# STM32F413CG_CS43L22.net
KiCad netlist of a schematic drawn in EAGLE
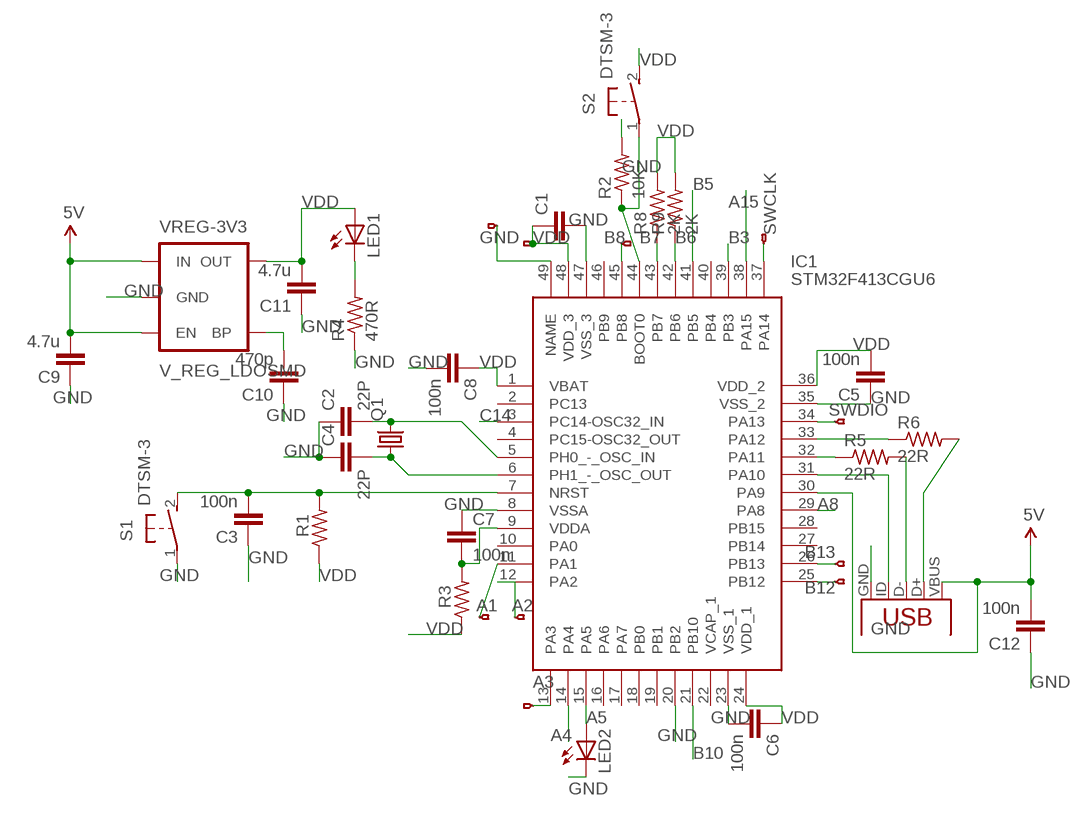
[diagram p0: schematic, sheet 1]
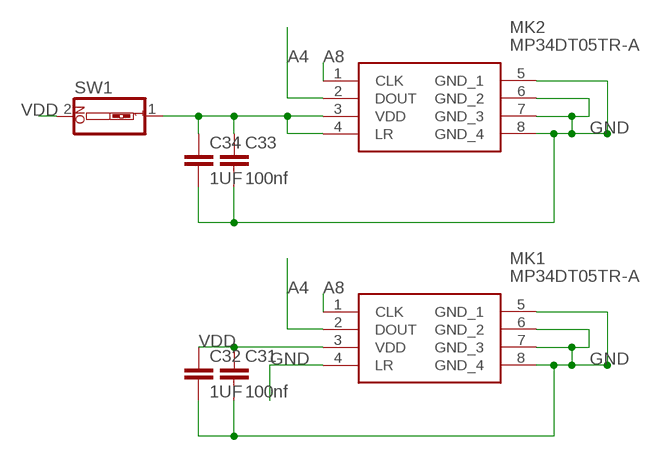
[diagram p1: schematic, sheet 2]
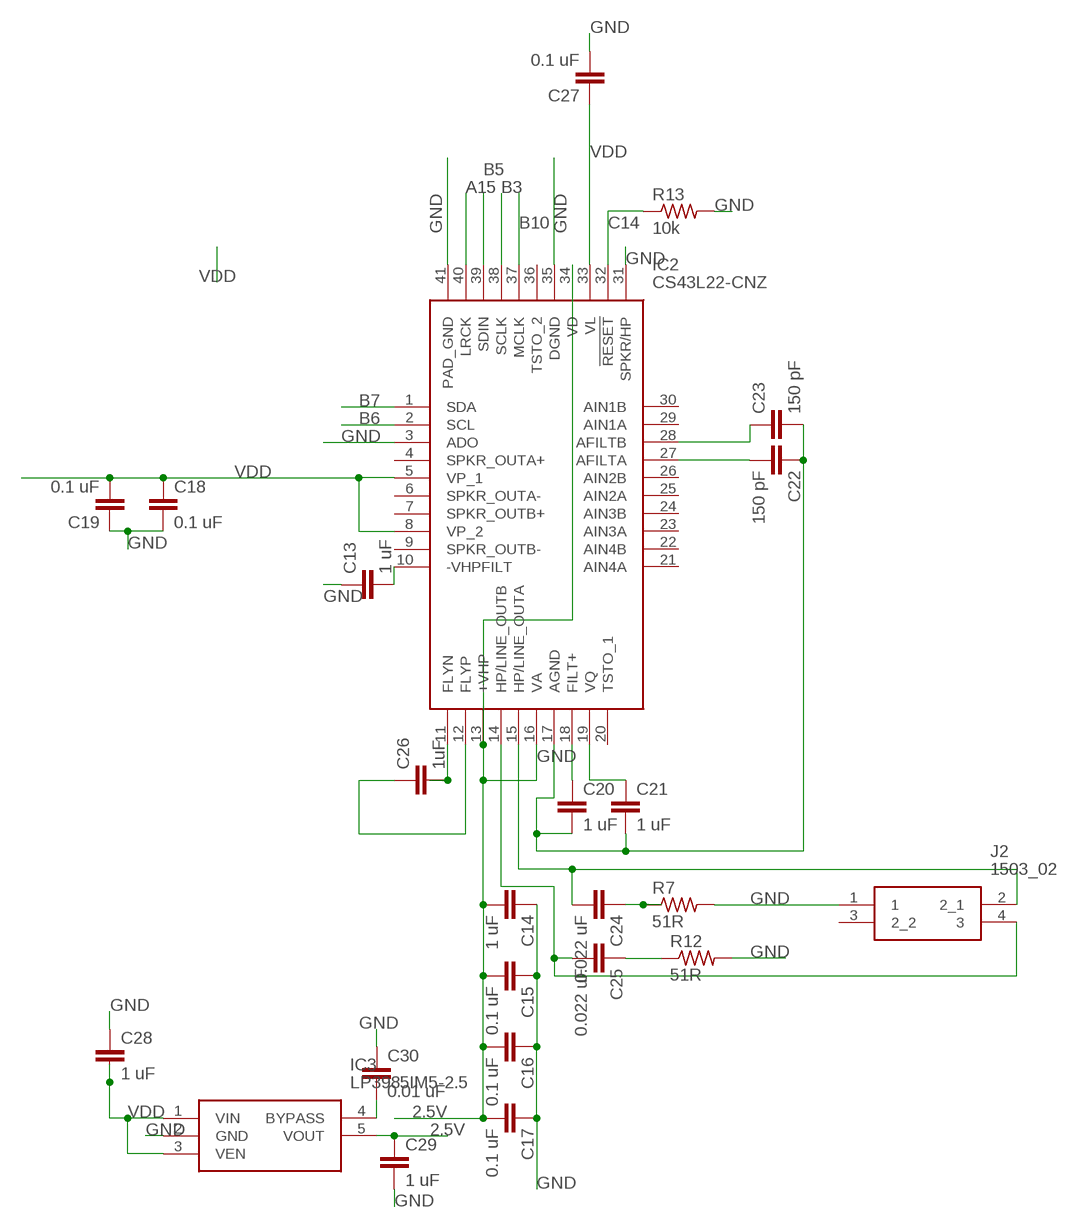
[diagram p2: schematic, sheet 3]

(export (version "E")
  (design (tool "Eeschema 10.0.6"))
  (components
    (comp (ref "C13")
      (value "1 uF")
      (footprint "eagle-import:CAP-PTH-SMALL-KIT")
      (libsource (lib "eagle-import") (part "CAPKIT"))
    )
    (comp (ref "C14")
      (value "1 uF")
      (footprint "eagle-import:CAP-PTH-SMALL-KIT")
      (libsource (lib "eagle-import") (part "CAPKIT"))
    )
    (comp (ref "C15")
      (value "0.1 uF")
      (footprint "eagle-import:CAP-PTH-SMALL-KIT")
      (libsource (lib "eagle-import") (part "CAPKIT"))
    )
    (comp (ref "C16")
      (value "0.1 uF")
      (footprint "eagle-import:CAP-PTH-SMALL-KIT")
      (libsource (lib "eagle-import") (part "CAPKIT"))
    )
    (comp (ref "C17")
      (value "0.1 uF")
      (footprint "eagle-import:CAP-PTH-SMALL-KIT")
      (libsource (lib "eagle-import") (part "CAPKIT"))
    )
    (comp (ref "C18")
      (value "0.1 uF")
      (footprint "eagle-import:CAP-PTH-SMALL-KIT")
      (libsource (lib "eagle-import") (part "CAPKIT"))
    )
    (comp (ref "C19")
      (value "0.1 uF")
      (footprint "eagle-import:CAP-PTH-SMALL-KIT")
      (libsource (lib "eagle-import") (part "CAPKIT"))
    )
    (comp (ref "C20")
      (value "1 uF")
      (footprint "eagle-import:CAP-PTH-SMALL-KIT")
      (libsource (lib "eagle-import") (part "CAPKIT"))
    )
    (comp (ref "C21")
      (value "1 uF")
      (footprint "eagle-import:CAP-PTH-SMALL-KIT")
      (libsource (lib "eagle-import") (part "CAPKIT"))
    )
    (comp (ref "C22")
      (value "150 pF")
      (footprint "eagle-import:CAP-PTH-SMALL-KIT")
      (libsource (lib "eagle-import") (part "CAPKIT"))
    )
    (comp (ref "C23")
      (value "150 pF")
      (footprint "eagle-import:CAP-PTH-SMALL-KIT")
      (libsource (lib "eagle-import") (part "CAPKIT"))
    )
    (comp (ref "C24")
      (value "0.022 uF")
      (footprint "eagle-import:CAP-PTH-SMALL-KIT")
      (libsource (lib "eagle-import") (part "CAPKIT"))
    )
    (comp (ref "C25")
      (value "0.022 uF")
      (footprint "eagle-import:CAP-PTH-SMALL-KIT")
      (libsource (lib "eagle-import") (part "CAPKIT"))
    )
    (comp (ref "C26")
      (value "1uF")
      (footprint "eagle-import:C2.5-3")
      (libsource (lib "eagle-import") (part "C2,5-3"))
    )
    (comp (ref "C27")
      (value "0.1 uF")
      (footprint "eagle-import:CAP-PTH-SMALL-KIT")
      (libsource (lib "eagle-import") (part "CAPKIT"))
    )
    (comp (ref "C28")
      (value "1 uF")
      (footprint "eagle-import:CAP-PTH-SMALL-KIT")
      (libsource (lib "eagle-import") (part "CAPKIT"))
    )
    (comp (ref "C29")
      (value "1 uF")
      (footprint "eagle-import:CAP-PTH-SMALL-KIT")
      (libsource (lib "eagle-import") (part "CAPKIT"))
    )
    (comp (ref "C30")
      (value "0.01 uF")
      (footprint "eagle-import:CAP-PTH-SMALL-KIT")
      (libsource (lib "eagle-import") (part "CAPKIT"))
    )
    (comp (ref "IC2")
      (value "CS43L22-CNZ")
      (footprint "eagle-import:QFN50P600X600X100-41N")
      (fields
        (field (name "MOUSER_PART_NUMBER") "777-CS43L22-CNZ")
        (field (name "RS_PART_NUMBER") "7165851P")
      )
      (libsource (lib "eagle-import") (part "CS43L22-CNZ"))
    )
    (comp (ref "IC3")
      (value "LP3985IM5-2.5")
      (footprint "eagle-import:SOT95P300X120-5N")
      (fields
        (field (name "MOUSER_PART_NUMBER") "926-LP3985IM5-25")
        (field (name "RS_PART_NUMBER") "4433167")
      )
      (libsource (lib "eagle-import") (part "LP3985IM5-2.5"))
    )
    (comp (ref "J2")
      (value "1503_02")
      (footprint "eagle-import:150302")
      (fields (field (name "MANUFACTURER_PART_NUMBER") "1503 02"))
      (libsource (lib "eagle-import") (part "1503_02"))
    )
    (comp (ref "R7")
      (value "51R")
      (footprint "eagle-import:0204V")
      (libsource (lib "eagle-import") (part "R-US_0204/2V"))
    )
    (comp (ref "R12")
      (value "51R")
      (footprint "eagle-import:0204V")
      (libsource (lib "eagle-import") (part "R-US_0204/2V"))
    )
    (comp (ref "R13")
      (value "10k")
      (footprint "eagle-import:0204V")
      (libsource (lib "eagle-import") (part "R-US_0204/2V"))
    )
    (comp (ref "C1")
      (value "C2,5-3")
      (footprint "eagle-import:C2.5-3")
      (libsource (lib "eagle-import") (part "C2,5-3"))
    )
    (comp (ref "C2")
      (value "22P")
      (footprint "eagle-import:C2.5-3")
      (libsource (lib "eagle-import") (part "C2,5-3"))
    )
    (comp (ref "C3")
      (value "100n")
      (footprint "eagle-import:C2.5-3")
      (libsource (lib "eagle-import") (part "C2,5-3"))
    )
    (comp (ref "C4")
      (value "22P")
      (footprint "eagle-import:C2.5-3")
      (libsource (lib "eagle-import") (part "C2,5-3"))
    )
    (comp (ref "C5")
      (value "100n")
      (footprint "eagle-import:C2.5-3")
      (libsource (lib "eagle-import") (part "C2,5-3"))
    )
    (comp (ref "C6")
      (value "100n")
      (footprint "eagle-import:C2.5-3")
      (libsource (lib "eagle-import") (part "C2,5-3"))
    )
    (comp (ref "C7")
      (value "100n")
      (footprint "eagle-import:C2.5-3")
      (libsource (lib "eagle-import") (part "C2,5-3"))
    )
    (comp (ref "C8")
      (value "100n")
      (footprint "eagle-import:C2.5-3")
      (libsource (lib "eagle-import") (part "C2,5-3"))
    )
    (comp (ref "C9")
      (value "4.7u")
      (footprint "eagle-import:C2.5-3")
      (libsource (lib "eagle-import") (part "C2,5-3"))
    )
    (comp (ref "C10")
      (value "470p")
      (footprint "eagle-import:C2.5-3")
      (libsource (lib "eagle-import") (part "C2,5-3"))
    )
    (comp (ref "C11")
      (value "4.7u")
      (footprint "eagle-import:C2.5-3")
      (libsource (lib "eagle-import") (part "C2,5-3"))
    )
    (comp (ref "C12")
      (value "100n")
      (footprint "eagle-import:C2.5-3")
      (libsource (lib "eagle-import") (part "C2,5-3"))
    )
    (comp (ref "IC1")
      (value "STM32F413CGU6")
      (footprint "eagle-import:QFN50P700X700X60-49N")
      (fields (field (name "MOUSER_PART_NUMBER") "511-STM32F413CGU6"))
      (libsource (lib "eagle-import") (part "STM32F413CGU6"))
    )
    (comp (ref "JP1")
      (value "HEADERHOLE-HEADERHOLE")
      (footprint "eagle-import:1X1-HEADER-HOLE")
      (libsource (lib "eagle-import") (part "HEADERHOLE-HEADERHOLE"))
    )
    (comp (ref "JP2")
      (value "HEADERHOLE-HEADERHOLE")
      (footprint "eagle-import:1X1-HEADER-HOLE")
      (libsource (lib "eagle-import") (part "HEADERHOLE-HEADERHOLE"))
    )
    (comp (ref "JP3")
      (value "HEADERHOLE-HEADERHOLE")
      (footprint "eagle-import:1X1-HEADER-HOLE")
      (libsource (lib "eagle-import") (part "HEADERHOLE-HEADERHOLE"))
    )
    (comp (ref "JP4")
      (value "HEADERHOLE-HEADERHOLE")
      (footprint "eagle-import:1X1-HEADER-HOLE")
      (libsource (lib "eagle-import") (part "HEADERHOLE-HEADERHOLE"))
    )
    (comp (ref "JP5")
      (value "HEADERHOLE-HEADERHOLE")
      (footprint "eagle-import:1X1-HEADER-HOLE")
      (libsource (lib "eagle-import") (part "HEADERHOLE-HEADERHOLE"))
    )
    (comp (ref "JP6")
      (value "HEADERHOLE-HEADERHOLE")
      (footprint "eagle-import:1X1-HEADER-HOLE")
      (libsource (lib "eagle-import") (part "HEADERHOLE-HEADERHOLE"))
    )
    (comp (ref "JP7")
      (value "HEADERHOLE-HEADERHOLE")
      (footprint "eagle-import:1X1-HEADER-HOLE")
      (libsource (lib "eagle-import") (part "HEADERHOLE-HEADERHOLE"))
    )
    (comp (ref "JP8")
      (value "HEADERHOLE-HEADERHOLE")
      (footprint "eagle-import:1X1-HEADER-HOLE")
      (libsource (lib "eagle-import") (part "HEADERHOLE-HEADERHOLE"))
    )
    (comp (ref "JP9")
      (value "HEADERHOLE-HEADERHOLE")
      (footprint "eagle-import:1X1-HEADER-HOLE")
      (libsource (lib "eagle-import") (part "HEADERHOLE-HEADERHOLE"))
    )
    (comp (ref "JP10")
      (value "HEADERHOLE-HEADERHOLE")
      (footprint "eagle-import:1X1-HEADER-HOLE")
      (libsource (lib "eagle-import") (part "HEADERHOLE-HEADERHOLE"))
    )
    (comp (ref "LED1")
      (value "LED0603")
      (footprint "eagle-import:LED-0603")
      (libsource (lib "eagle-import") (part "LED0603"))
    )
    (comp (ref "LED2")
      (value "LED0603")
      (footprint "eagle-import:LED-0603")
      (libsource (lib "eagle-import") (part "LED0603"))
    )
    (comp (ref "Q1")
      (value "CRYSTALHC49S")
      (footprint "eagle-import:HC49_S")
      (libsource (lib "eagle-import") (part "CRYSTALHC49S"))
    )
    (comp (ref "R1")
      (value "R-US_0204/2V")
      (footprint "eagle-import:0204V")
      (libsource (lib "eagle-import") (part "R-US_0204/2V"))
    )
    (comp (ref "R2")
      (value "10K")
      (footprint "eagle-import:0204V")
      (libsource (lib "eagle-import") (part "R-US_0204/2V"))
    )
    (comp (ref "R3")
      (value "R-US_0204/2V")
      (footprint "eagle-import:0204V")
      (libsource (lib "eagle-import") (part "R-US_0204/2V"))
    )
    (comp (ref "R4")
      (value "470R")
      (footprint "eagle-import:0204V")
      (libsource (lib "eagle-import") (part "R-US_0204/2V"))
    )
    (comp (ref "R5")
      (value "22R")
      (footprint "eagle-import:0204V")
      (libsource (lib "eagle-import") (part "R-US_0204/2V"))
    )
    (comp (ref "R6")
      (value "22R")
      (footprint "eagle-import:0204V")
      (libsource (lib "eagle-import") (part "R-US_0204/2V"))
    )
    (comp (ref "R8")
      (value "2K")
      (footprint "eagle-import:0204V")
      (libsource (lib "eagle-import") (part "R-US_0204/2V"))
    )
    (comp (ref "R9")
      (value "2K")
      (footprint "eagle-import:0204V")
      (libsource (lib "eagle-import") (part "R-US_0204/2V"))
    )
    (comp (ref "S1")
      (value "DTSM-3")
      (footprint "eagle-import:DTSM-3")
      (libsource (lib "eagle-import") (part "DTSM-3"))
    )
    (comp (ref "S2")
      (value "DTSM-3")
      (footprint "eagle-import:DTSM-3")
      (libsource (lib "eagle-import") (part "DTSM-3"))
    )
    (comp (ref "VREG-3V3")
      (value "V_REG_LDOSMD")
      (footprint "eagle-import:SOT23-5")
      (libsource (lib "eagle-import") (part "V_REG_LDOSMD"))
    )
    (comp (ref "X1")
      (value "USB-MICROB-SMD")
      (footprint "eagle-import:USB-MICROB-SMD")
      (libsource (lib "eagle-import") (part "USB-MICROB-SMD"))
    )
    (comp (ref "C31")
      (value "100nf")
      (footprint "eagle-import:C2.5-2")
      (libsource (lib "eagle-import") (part "C2.5/2"))
    )
    (comp (ref "C32")
      (value "1UF")
      (footprint "eagle-import:C2.5-2")
      (libsource (lib "eagle-import") (part "C2.5/2"))
    )
    (comp (ref "C33")
      (value "100nf")
      (footprint "eagle-import:C2.5-2")
      (libsource (lib "eagle-import") (part "C2.5/2"))
    )
    (comp (ref "C34")
      (value "1UF")
      (footprint "eagle-import:C2.5-2")
      (libsource (lib "eagle-import") (part "C2.5/2"))
    )
    (comp (ref "MK1")
      (value "MP34DT05TR-A")
      (footprint "eagle-import:MP34DT05TRA")
      (fields (field (name "MOUSER_PART_NUMBER") "511-MP34DT05TR-A"))
      (libsource (lib "eagle-import") (part "MP34DT05TR-A"))
    )
    (comp (ref "MK2")
      (value "MP34DT05TR-A")
      (footprint "eagle-import:MP34DT05TRA")
      (fields (field (name "MOUSER_PART_NUMBER") "511-MP34DT05TR-A"))
      (libsource (lib "eagle-import") (part "MP34DT05TR-A"))
    )
    (comp (ref "SW1")
      (value "SW_DIP-1")
      (footprint "eagle-import:EDG-01")
      (libsource (lib "eagle-import") (part "SW_DIP-1"))
    )
  )
  (nets
    (net (code "1") (name "2.5V") (class "Default")
      (node (ref "C14") (pin "2") (pinfunction "2_2") (pintype "passive"))
      (node (ref "C15") (pin "2") (pinfunction "2_2") (pintype "passive"))
      (node (ref "C16") (pin "2") (pinfunction "2_2") (pintype "passive"))
      (node (ref "C17") (pin "2") (pinfunction "2_2") (pintype "passive"))
      (node (ref "C29") (pin "1") (pinfunction "1_1") (pintype "passive"))
      (node (ref "IC2") (pin "13") (pinfunction "+VHP_13") (pintype "bidirectional"))
      (node (ref "IC2") (pin "16") (pinfunction "VA_16") (pintype "bidirectional"))
      (node (ref "IC2") (pin "34") (pinfunction "VD_34") (pintype "bidirectional"))
      (node (ref "IC3") (pin "5") (pinfunction "VOUT_5") (pintype "bidirectional"))
    )
    (net (code "2") (name "5V") (class "Default")
      (node (ref "C12") (pin "2") (pinfunction "2_2") (pintype "passive"))
      (node (ref "C9") (pin "2") (pinfunction "2_2") (pintype "passive"))
      (node (ref "IC1") (pin "30") (pinfunction "PA9_30") (pintype "bidirectional"))
      (node (ref "VREG-3V3") (pin "1") (pinfunction "IN_1") (pintype "input"))
      (node (ref "VREG-3V3") (pin "3") (pinfunction "EN_3") (pintype "input"))
      (node (ref "X1") (pin "VBUS") (pinfunction "VBUS_VBUS") (pintype "bidirectional"))
    )
    (net (code "3") (name "A1") (class "Default")
      (node (ref "IC1") (pin "11") (pinfunction "PA1_11") (pintype "bidirectional"))
      (node (ref "JP8") (pin "1") (pinfunction "P$1_1") (pintype "bidirectional"))
    )
    (net (code "4") (name "A2") (class "Default")
      (node (ref "IC1") (pin "12") (pinfunction "PA2_12") (pintype "bidirectional"))
      (node (ref "JP9") (pin "1") (pinfunction "P$1_1") (pintype "bidirectional"))
    )
    (net (code "5") (name "A3") (class "Default")
      (node (ref "IC1") (pin "13") (pinfunction "PA3_13") (pintype "bidirectional"))
      (node (ref "JP10") (pin "1") (pinfunction "P$1_1") (pintype "bidirectional"))
    )
    (net (code "6") (name "A4") (class "Default")
      (node (ref "IC1") (pin "14") (pinfunction "PA4_14") (pintype "bidirectional"))
      (node (ref "MK1") (pin "2") (pinfunction "DOUT_2") (pintype "bidirectional"))
      (node (ref "MK2") (pin "2") (pinfunction "DOUT_2") (pintype "bidirectional"))
    )
    (net (code "7") (name "A5") (class "Default")
      (node (ref "IC1") (pin "15") (pinfunction "PA5_15") (pintype "bidirectional"))
      (node (ref "LED2") (pin "A") (pinfunction "A_A") (pintype "passive"))
    )
    (net (code "8") (name "A8") (class "Default")
      (node (ref "IC1") (pin "29") (pinfunction "PA8_29") (pintype "bidirectional"))
      (node (ref "MK1") (pin "1") (pinfunction "CLK_1") (pintype "bidirectional"))
      (node (ref "MK2") (pin "1") (pinfunction "CLK_1") (pintype "bidirectional"))
    )
    (net (code "9") (name "A15") (class "Default")
      (node (ref "IC1") (pin "38") (pinfunction "PA15_38") (pintype "bidirectional"))
      (node (ref "IC2") (pin "40") (pinfunction "LRCK_40") (pintype "bidirectional"))
    )
    (net (code "10") (name "B3") (class "Default")
      (node (ref "IC1") (pin "39") (pinfunction "PB3_39") (pintype "bidirectional"))
      (node (ref "IC2") (pin "38") (pinfunction "SCLK_38") (pintype "bidirectional"))
    )
    (net (code "11") (name "B5") (class "Default")
      (node (ref "IC1") (pin "41") (pinfunction "PB5_41") (pintype "bidirectional"))
      (node (ref "IC2") (pin "39") (pinfunction "SDIN_39") (pintype "bidirectional"))
    )
    (net (code "12") (name "B6") (class "Default")
      (node (ref "IC1") (pin "42") (pinfunction "PB6_42") (pintype "bidirectional"))
      (node (ref "IC2") (pin "2") (pinfunction "SCL_2") (pintype "bidirectional"))
      (node (ref "R9") (pin "1") (pinfunction "1_1") (pintype "passive"))
    )
    (net (code "13") (name "B7") (class "Default")
      (node (ref "IC1") (pin "43") (pinfunction "PB7_43") (pintype "bidirectional"))
      (node (ref "IC2") (pin "1") (pinfunction "SDA_1") (pintype "bidirectional"))
      (node (ref "R8") (pin "1") (pinfunction "1_1") (pintype "passive"))
    )
    (net (code "14") (name "B8") (class "Default")
      (node (ref "IC1") (pin "45") (pinfunction "PB8_45") (pintype "bidirectional"))
      (node (ref "JP5") (pin "1") (pinfunction "P$1_1") (pintype "bidirectional"))
    )
    (net (code "15") (name "B10") (class "Default")
      (node (ref "IC1") (pin "21") (pinfunction "PB10_21") (pintype "bidirectional"))
      (node (ref "IC2") (pin "37") (pinfunction "MCLK_37") (pintype "bidirectional"))
    )
    (net (code "16") (name "B12") (class "Default")
      (node (ref "IC1") (pin "25") (pinfunction "PB12_25") (pintype "bidirectional"))
      (node (ref "JP7") (pin "1") (pinfunction "P$1_1") (pintype "bidirectional"))
    )
    (net (code "17") (name "B13") (class "Default")
      (node (ref "IC1") (pin "26") (pinfunction "PB13_26") (pintype "bidirectional"))
      (node (ref "JP6") (pin "1") (pinfunction "P$1_1") (pintype "bidirectional"))
    )
    (net (code "18") (name "C14") (class "Default")
      (node (ref "IC1") (pin "3") (pinfunction "PC14-OSC32_IN_3") (pintype "bidirectional"))
      (node (ref "IC2") (pin "32") (pinfunction "~{RESET}_32") (pintype "bidirectional"))
      (node (ref "R13") (pin "1") (pinfunction "1_1") (pintype "passive"))
    )
    (net (code "19") (name "GND") (class "Default")
      (node (ref "C1") (pin "2") (pinfunction "2_2") (pintype "passive"))
      (node (ref "C10") (pin "1") (pinfunction "1_1") (pintype "passive"))
      (node (ref "C11") (pin "1") (pinfunction "1_1") (pintype "passive"))
      (node (ref "C12") (pin "1") (pinfunction "1_1") (pintype "passive"))
      (node (ref "C13") (pin "1") (pinfunction "1_1") (pintype "passive"))
      (node (ref "C14") (pin "1") (pinfunction "1_1") (pintype "passive"))
      (node (ref "C15") (pin "1") (pinfunction "1_1") (pintype "passive"))
      (node (ref "C16") (pin "1") (pinfunction "1_1") (pintype "passive"))
      (node (ref "C17") (pin "1") (pinfunction "1_1") (pintype "passive"))
      (node (ref "C18") (pin "2") (pinfunction "2_2") (pintype "passive"))
      (node (ref "C19") (pin "1") (pinfunction "1_1") (pintype "passive"))
      (node (ref "C2") (pin "1") (pinfunction "1_1") (pintype "passive"))
      (node (ref "C20") (pin "2") (pinfunction "2_2") (pintype "passive"))
      (node (ref "C21") (pin "2") (pinfunction "2_2") (pintype "passive"))
      (node (ref "C22") (pin "1") (pinfunction "1_1") (pintype "passive"))
      (node (ref "C23") (pin "2") (pinfunction "2_2") (pintype "passive"))
      (node (ref "C27") (pin "2") (pinfunction "2_2") (pintype "passive"))
      (node (ref "C28") (pin "1") (pinfunction "1_1") (pintype "passive"))
      (node (ref "C29") (pin "2") (pinfunction "2_2") (pintype "passive"))
      (node (ref "C3") (pin "1") (pinfunction "1_1") (pintype "passive"))
      (node (ref "C30") (pin "1") (pinfunction "1_1") (pintype "passive"))
      (node (ref "C31") (pin "2") (pinfunction "2_2") (pintype "passive"))
      (node (ref "C32") (pin "2") (pinfunction "2_2") (pintype "passive"))
      (node (ref "C33") (pin "2") (pinfunction "2_2") (pintype "passive"))
      (node (ref "C34") (pin "2") (pinfunction "2_2") (pintype "passive"))
      (node (ref "C4") (pin "1") (pinfunction "1_1") (pintype "passive"))
      (node (ref "C5") (pin "1") (pinfunction "1_1") (pintype "passive"))
      (node (ref "C6") (pin "2") (pinfunction "2_2") (pintype "passive"))
      (node (ref "C7") (pin "1") (pinfunction "1_1") (pintype "passive"))
      (node (ref "C8") (pin "2") (pinfunction "2_2") (pintype "passive"))
      (node (ref "C9") (pin "1") (pinfunction "1_1") (pintype "passive"))
      (node (ref "IC1") (pin "20") (pinfunction "PB2_20") (pintype "bidirectional"))
      (node (ref "IC1") (pin "23") (pinfunction "VSS_1_23") (pintype "power_in"))
      (node (ref "IC1") (pin "35") (pinfunction "VSS_2_35") (pintype "power_in"))
      (node (ref "IC1") (pin "47") (pinfunction "VSS_3_47") (pintype "power_in"))
      (node (ref "IC1") (pin "49") (pinfunction "NAME_49") (pintype "bidirectional"))
      (node (ref "IC1") (pin "8") (pinfunction "VSSA_8") (pintype "power_in"))
      (node (ref "IC2") (pin "17") (pinfunction "AGND_17") (pintype "bidirectional"))
      (node (ref "IC2") (pin "3") (pinfunction "ADO_3") (pintype "bidirectional"))
      (node (ref "IC2") (pin "31") (pinfunction "SPKR/HP_31") (pintype "bidirectional"))
      (node (ref "IC2") (pin "35") (pinfunction "DGND_35") (pintype "bidirectional"))
      (node (ref "IC2") (pin "41") (pinfunction "PAD_GND_41") (pintype "bidirectional"))
      (node (ref "IC3") (pin "2") (pinfunction "GND_2") (pintype "bidirectional"))
      (node (ref "J2") (pin "1") (pinfunction "1_1") (pintype "bidirectional"))
      (node (ref "JP1") (pin "1") (pinfunction "P$1_1") (pintype "bidirectional"))
      (node (ref "LED2") (pin "C") (pinfunction "C_C") (pintype "passive"))
      (node (ref "MK1") (pin "4") (pinfunction "LR_4") (pintype "bidirectional"))
      (node (ref "MK1") (pin "5") (pinfunction "GND_1_5") (pintype "bidirectional"))
      (node (ref "MK1") (pin "6") (pinfunction "GND_2_6") (pintype "bidirectional"))
      (node (ref "MK1") (pin "7") (pinfunction "GND_3_7") (pintype "bidirectional"))
      (node (ref "MK1") (pin "8") (pinfunction "GND_4_8") (pintype "bidirectional"))
      (node (ref "MK2") (pin "5") (pinfunction "GND_1_5") (pintype "bidirectional"))
      (node (ref "MK2") (pin "6") (pinfunction "GND_2_6") (pintype "bidirectional"))
      (node (ref "MK2") (pin "7") (pinfunction "GND_3_7") (pintype "bidirectional"))
      (node (ref "MK2") (pin "8") (pinfunction "GND_4_8") (pintype "bidirectional"))
      (node (ref "R12") (pin "2") (pinfunction "2_2") (pintype "passive"))
      (node (ref "R13") (pin "2") (pinfunction "2_2") (pintype "passive"))
      (node (ref "R2") (pin "2") (pinfunction "2_2") (pintype "passive"))
      (node (ref "R4") (pin "1") (pinfunction "1_1") (pintype "passive"))
      (node (ref "R7") (pin "2") (pinfunction "2_2") (pintype "passive"))
      (node (ref "S1") (pin "1") (pinfunction "1_1") (pintype "passive"))
      (node (ref "VREG-3V3") (pin "2") (pinfunction "GND_2") (pintype "input"))
      (node (ref "X1") (pin "GND") (pinfunction "GND_GND") (pintype "bidirectional"))
    )
    (net (code "20") (name "Net-(C24-Pad1)") (class "Default")
      (node (ref "C24") (pin "1") (pinfunction "1_1") (pintype "passive"))
      (node (ref "R7") (pin "1") (pinfunction "1_1") (pintype "passive"))
    )
    (net (code "21") (name "Net-(C25-Pad1)") (class "Default")
      (node (ref "C25") (pin "1") (pinfunction "1_1") (pintype "passive"))
      (node (ref "R12") (pin "1") (pinfunction "1_1") (pintype "passive"))
    )
    (net (code "22") (name "Net-(IC1-BOOT0)") (class "Default")
      (node (ref "IC1") (pin "44") (pinfunction "BOOT0_44") (pintype "bidirectional"))
      (node (ref "R2") (pin "1") (pinfunction "1_1") (pintype "passive"))
      (node (ref "S2") (pin "1") (pinfunction "1_1") (pintype "passive"))
    )
    (net (code "23") (name "Net-(IC1-NRST)") (class "Default")
      (node (ref "C3") (pin "2") (pinfunction "2_2") (pintype "passive"))
      (node (ref "IC1") (pin "7") (pinfunction "NRST_7") (pintype "bidirectional"))
      (node (ref "R1") (pin "2") (pinfunction "2_2") (pintype "passive"))
      (node (ref "S1") (pin "2") (pinfunction "2_2") (pintype "passive"))
    )
    (net (code "24") (name "Net-(IC1-PA10)") (class "Default")
      (node (ref "IC1") (pin "31") (pinfunction "PA10_31") (pintype "bidirectional"))
      (node (ref "X1") (pin "ID") (pinfunction "ID_ID") (pintype "bidirectional"))
    )
    (net (code "25") (name "Net-(IC1-PA11)") (class "Default")
      (node (ref "IC1") (pin "32") (pinfunction "PA11_32") (pintype "bidirectional"))
      (node (ref "R5") (pin "1") (pinfunction "1_1") (pintype "passive"))
    )
    (net (code "26") (name "Net-(IC1-PA12)") (class "Default")
      (node (ref "IC1") (pin "33") (pinfunction "PA12_33") (pintype "bidirectional"))
      (node (ref "R6") (pin "1") (pinfunction "1_1") (pintype "passive"))
    )
    (net (code "27") (name "Net-(IC1-PH0_-_OSC_IN)") (class "Default")
      (node (ref "C2") (pin "2") (pinfunction "2_2") (pintype "passive"))
      (node (ref "IC1") (pin "5") (pinfunction "PH0_-_OSC_IN_5") (pintype "bidirectional"))
      (node (ref "Q1") (pin "2") (pinfunction "2_2") (pintype "passive"))
    )
    (net (code "28") (name "Net-(IC1-PH1_-_OSC_OUT)") (class "Default")
      (node (ref "C4") (pin "2") (pinfunction "2_2") (pintype "passive"))
      (node (ref "IC1") (pin "6") (pinfunction "PH1_-_OSC_OUT_6") (pintype "bidirectional"))
      (node (ref "Q1") (pin "1") (pinfunction "1_1") (pintype "passive"))
    )
    (net (code "29") (name "Net-(IC1-VDDA)") (class "Default")
      (node (ref "C7") (pin "2") (pinfunction "2_2") (pintype "passive"))
      (node (ref "IC1") (pin "9") (pinfunction "VDDA_9") (pintype "power_in"))
      (node (ref "R3") (pin "2") (pinfunction "2_2") (pintype "passive"))
    )
    (net (code "30") (name "Net-(IC2--VHPFILT)") (class "Default")
      (node (ref "C13") (pin "2") (pinfunction "2_2") (pintype "passive"))
      (node (ref "IC2") (pin "10") (pinfunction "-VHPFILT_10") (pintype "bidirectional"))
    )
    (net (code "31") (name "Net-(IC2-AFILTA)") (class "Default")
      (node (ref "C22") (pin "2") (pinfunction "2_2") (pintype "passive"))
      (node (ref "IC2") (pin "27") (pinfunction "AFILTA_27") (pintype "bidirectional"))
    )
    (net (code "32") (name "Net-(IC2-AFILTB)") (class "Default")
      (node (ref "C23") (pin "1") (pinfunction "1_1") (pintype "passive"))
      (node (ref "IC2") (pin "28") (pinfunction "AFILTB_28") (pintype "bidirectional"))
    )
    (net (code "33") (name "Net-(IC2-FILT+)") (class "Default")
      (node (ref "C20") (pin "1") (pinfunction "1_1") (pintype "passive"))
      (node (ref "IC2") (pin "18") (pinfunction "FILT+_18") (pintype "bidirectional"))
    )
    (net (code "34") (name "Net-(IC2-FLYN)") (class "Default")
      (node (ref "C26") (pin "2") (pinfunction "2_2") (pintype "passive"))
      (node (ref "IC2") (pin "11") (pinfunction "FLYN_11") (pintype "bidirectional"))
    )
    (net (code "35") (name "Net-(IC2-FLYP)") (class "Default")
      (node (ref "C26") (pin "1") (pinfunction "1_1") (pintype "passive"))
      (node (ref "IC2") (pin "12") (pinfunction "FLYP_12") (pintype "bidirectional"))
    )
    (net (code "36") (name "Net-(IC2-HP{slash}LINE_OUTA)") (class "Default")
      (node (ref "C24") (pin "2") (pinfunction "2_2") (pintype "passive"))
      (node (ref "IC2") (pin "15") (pinfunction "HP/LINE_OUTA_15") (pintype "bidirectional"))
      (node (ref "J2") (pin "2") (pinfunction "2_1_2") (pintype "bidirectional"))
    )
    (net (code "37") (name "Net-(IC2-HP{slash}LINE_OUTB)") (class "Default")
      (node (ref "C25") (pin "2") (pinfunction "2_2") (pintype "passive"))
      (node (ref "IC2") (pin "14") (pinfunction "HP/LINE_OUTB_14") (pintype "bidirectional"))
      (node (ref "J2") (pin "4") (pinfunction "3_4") (pintype "bidirectional"))
    )
    (net (code "38") (name "Net-(IC2-VQ)") (class "Default")
      (node (ref "C21") (pin "1") (pinfunction "1_1") (pintype "passive"))
      (node (ref "IC2") (pin "19") (pinfunction "VQ_19") (pintype "bidirectional"))
    )
    (net (code "39") (name "Net-(IC3-BYPASS)") (class "Default")
      (node (ref "C30") (pin "2") (pinfunction "2_2") (pintype "passive"))
      (node (ref "IC3") (pin "4") (pinfunction "BYPASS_4") (pintype "bidirectional"))
    )
    (net (code "40") (name "Net-(LED1-PadC)") (class "Default")
      (node (ref "LED1") (pin "C") (pinfunction "C_C") (pintype "passive"))
      (node (ref "R4") (pin "2") (pinfunction "2_2") (pintype "passive"))
    )
    (net (code "41") (name "Net-(MK2-LR)") (class "Default")
      (node (ref "C33") (pin "1") (pinfunction "1_1") (pintype "passive"))
      (node (ref "C34") (pin "1") (pinfunction "1_1") (pintype "passive"))
      (node (ref "MK2") (pin "3") (pinfunction "VDD_3") (pintype "bidirectional"))
      (node (ref "MK2") (pin "4") (pinfunction "LR_4") (pintype "bidirectional"))
      (node (ref "SW1") (pin "1") (pinfunction "1_1") (pintype "passive"))
    )
    (net (code "42") (name "Net-(R5-Pad2)") (class "Default")
      (node (ref "R5") (pin "2") (pinfunction "2_2") (pintype "passive"))
      (node (ref "X1") (pin "D-") (pinfunction "D-_D-") (pintype "bidirectional"))
    )
    (net (code "43") (name "Net-(R6-Pad2)") (class "Default")
      (node (ref "R6") (pin "2") (pinfunction "2_2") (pintype "passive"))
      (node (ref "X1") (pin "D+") (pinfunction "D+_D+") (pintype "bidirectional"))
    )
    (net (code "44") (name "Net-(VREG-3V3-BP)") (class "Default")
      (node (ref "C10") (pin "2") (pinfunction "2_2") (pintype "passive"))
      (node (ref "VREG-3V3") (pin "4") (pinfunction "BP_4") (pintype "input"))
    )
    (net (code "45") (name "SWCLK") (class "Default")
      (node (ref "IC1") (pin "37") (pinfunction "PA14_37") (pintype "bidirectional"))
      (node (ref "JP2") (pin "1") (pinfunction "P$1_1") (pintype "bidirectional"))
    )
    (net (code "46") (name "SWDIO") (class "Default")
      (node (ref "IC1") (pin "34") (pinfunction "PA13_34") (pintype "bidirectional"))
      (node (ref "JP3") (pin "1") (pinfunction "P$1_1") (pintype "bidirectional"))
    )
    (net (code "47") (name "VCAP_1") (class "Default")
      (node (ref "IC1") (pin "22") (pinfunction "VCAP_1_22") (pintype "power_in"))
    )
    (net (code "48") (name "VDD") (class "Default")
      (node (ref "C1") (pin "1") (pinfunction "1_1") (pintype "passive"))
      (node (ref "C11") (pin "2") (pinfunction "2_2") (pintype "passive"))
      (node (ref "C18") (pin "1") (pinfunction "1_1") (pintype "passive"))
      (node (ref "C19") (pin "2") (pinfunction "2_2") (pintype "passive"))
      (node (ref "C27") (pin "1") (pinfunction "1_1") (pintype "passive"))
      (node (ref "C28") (pin "2") (pinfunction "2_2") (pintype "passive"))
      (node (ref "C31") (pin "1") (pinfunction "1_1") (pintype "passive"))
      (node (ref "C32") (pin "1") (pinfunction "1_1") (pintype "passive"))
      (node (ref "C5") (pin "2") (pinfunction "2_2") (pintype "passive"))
      (node (ref "C6") (pin "1") (pinfunction "1_1") (pintype "passive"))
      (node (ref "C8") (pin "1") (pinfunction "1_1") (pintype "passive"))
      (node (ref "IC1") (pin "1") (pinfunction "VBAT_1") (pintype "power_in"))
      (node (ref "IC1") (pin "24") (pinfunction "VDD_1_24") (pintype "power_in"))
      (node (ref "IC1") (pin "36") (pinfunction "VDD_2_36") (pintype "power_in"))
      (node (ref "IC1") (pin "48") (pinfunction "VDD_3_48") (pintype "power_in"))
      (node (ref "IC2") (pin "33") (pinfunction "VL_33") (pintype "bidirectional"))
      (node (ref "IC2") (pin "5") (pinfunction "VP_1_5") (pintype "bidirectional"))
      (node (ref "IC2") (pin "8") (pinfunction "VP_2_8") (pintype "bidirectional"))
      (node (ref "IC3") (pin "1") (pinfunction "VIN_1") (pintype "bidirectional"))
      (node (ref "IC3") (pin "3") (pinfunction "VEN_3") (pintype "bidirectional"))
      (node (ref "JP4") (pin "1") (pinfunction "P$1_1") (pintype "bidirectional"))
      (node (ref "LED1") (pin "A") (pinfunction "A_A") (pintype "passive"))
      (node (ref "MK1") (pin "3") (pinfunction "VDD_3") (pintype "bidirectional"))
      (node (ref "R1") (pin "1") (pinfunction "1_1") (pintype "passive"))
      (node (ref "R3") (pin "1") (pinfunction "1_1") (pintype "passive"))
      (node (ref "R8") (pin "2") (pinfunction "2_2") (pintype "passive"))
      (node (ref "R9") (pin "2") (pinfunction "2_2") (pintype "passive"))
      (node (ref "S2") (pin "2") (pinfunction "2_2") (pintype "passive"))
      (node (ref "SW1") (pin "2") (pinfunction "2_2") (pintype "passive"))
      (node (ref "VREG-3V3") (pin "5") (pinfunction "OUT_5") (pintype "passive"))
    )
    (net (code "49") (name "unconnected-(IC1-PA0-Pad10)") (class "Default")
      (node (ref "IC1") (pin "10") (pinfunction "PA0_10") (pintype "bidirectional"))
    )
    (net (code "50") (name "unconnected-(IC1-PA6-Pad16)") (class "Default")
      (node (ref "IC1") (pin "16") (pinfunction "PA6_16") (pintype "bidirectional"))
    )
    (net (code "51") (name "unconnected-(IC1-PA7-Pad17)") (class "Default")
      (node (ref "IC1") (pin "17") (pinfunction "PA7_17") (pintype "bidirectional"))
    )
    (net (code "52") (name "unconnected-(IC1-PB0-Pad18)") (class "Default")
      (node (ref "IC1") (pin "18") (pinfunction "PB0_18") (pintype "bidirectional"))
    )
    (net (code "53") (name "unconnected-(IC1-PB1-Pad19)") (class "Default")
      (node (ref "IC1") (pin "19") (pinfunction "PB1_19") (pintype "bidirectional"))
    )
    (net (code "54") (name "unconnected-(IC1-PB4-Pad40)") (class "Default")
      (node (ref "IC1") (pin "40") (pinfunction "PB4_40") (pintype "bidirectional"))
    )
    (net (code "55") (name "unconnected-(IC1-PB9-Pad46)") (class "Default")
      (node (ref "IC1") (pin "46") (pinfunction "PB9_46") (pintype "bidirectional"))
    )
    (net (code "56") (name "unconnected-(IC1-PB14-Pad27)") (class "Default")
      (node (ref "IC1") (pin "27") (pinfunction "PB14_27") (pintype "bidirectional"))
    )
    (net (code "57") (name "unconnected-(IC1-PB15-Pad28)") (class "Default")
      (node (ref "IC1") (pin "28") (pinfunction "PB15_28") (pintype "bidirectional"))
    )
    (net (code "58") (name "unconnected-(IC1-PC13-Pad2)") (class "Default")
      (node (ref "IC1") (pin "2") (pinfunction "PC13_2") (pintype "bidirectional"))
    )
    (net (code "59") (name "unconnected-(IC1-PC15-OSC32_OUT-Pad4)") (class "Default")
      (node (ref "IC1") (pin "4") (pinfunction "PC15-OSC32_OUT_4") (pintype "bidirectional"))
    )
    (net (code "60") (name "unconnected-(IC2-AIN1A-Pad29)") (class "Default")
      (node (ref "IC2") (pin "29") (pinfunction "AIN1A_29") (pintype "bidirectional"))
    )
    (net (code "61") (name "unconnected-(IC2-AIN1B-Pad30)") (class "Default")
      (node (ref "IC2") (pin "30") (pinfunction "AIN1B_30") (pintype "bidirectional"))
    )
    (net (code "62") (name "unconnected-(IC2-AIN2A-Pad25)") (class "Default")
      (node (ref "IC2") (pin "25") (pinfunction "AIN2A_25") (pintype "bidirectional"))
    )
    (net (code "63") (name "unconnected-(IC2-AIN2B-Pad26)") (class "Default")
      (node (ref "IC2") (pin "26") (pinfunction "AIN2B_26") (pintype "bidirectional"))
    )
    (net (code "64") (name "unconnected-(IC2-AIN3A-Pad23)") (class "Default")
      (node (ref "IC2") (pin "23") (pinfunction "AIN3A_23") (pintype "bidirectional"))
    )
    (net (code "65") (name "unconnected-(IC2-AIN3B-Pad24)") (class "Default")
      (node (ref "IC2") (pin "24") (pinfunction "AIN3B_24") (pintype "bidirectional"))
    )
    (net (code "66") (name "unconnected-(IC2-AIN4A-Pad21)") (class "Default")
      (node (ref "IC2") (pin "21") (pinfunction "AIN4A_21") (pintype "bidirectional"))
    )
    (net (code "67") (name "unconnected-(IC2-AIN4B-Pad22)") (class "Default")
      (node (ref "IC2") (pin "22") (pinfunction "AIN4B_22") (pintype "bidirectional"))
    )
    (net (code "68") (name "unconnected-(IC2-SPKR_OUTA+-Pad4)") (class "Default")
      (node (ref "IC2") (pin "4") (pinfunction "SPKR_OUTA+_4") (pintype "bidirectional"))
    )
    (net (code "69") (name "unconnected-(IC2-SPKR_OUTA--Pad6)") (class "Default")
      (node (ref "IC2") (pin "6") (pinfunction "SPKR_OUTA-_6") (pintype "bidirectional"))
    )
    (net (code "70") (name "unconnected-(IC2-SPKR_OUTB+-Pad7)") (class "Default")
      (node (ref "IC2") (pin "7") (pinfunction "SPKR_OUTB+_7") (pintype "bidirectional"))
    )
    (net (code "71") (name "unconnected-(IC2-SPKR_OUTB--Pad9)") (class "Default")
      (node (ref "IC2") (pin "9") (pinfunction "SPKR_OUTB-_9") (pintype "bidirectional"))
    )
    (net (code "72") (name "unconnected-(IC2-TSTO_1-Pad20)") (class "Default")
      (node (ref "IC2") (pin "20") (pinfunction "TSTO_1_20") (pintype "bidirectional"))
    )
    (net (code "73") (name "unconnected-(IC2-TSTO_2-Pad36)") (class "Default")
      (node (ref "IC2") (pin "36") (pinfunction "TSTO_2_36") (pintype "bidirectional"))
    )
    (net (code "74") (name "unconnected-(J2-2_2-Pad3)") (class "Default")
      (node (ref "J2") (pin "3") (pinfunction "2_2_3") (pintype "bidirectional"))
    )
  )
)
